# Power.net
KiCad netlist of a schematic drawn in Altium Designer
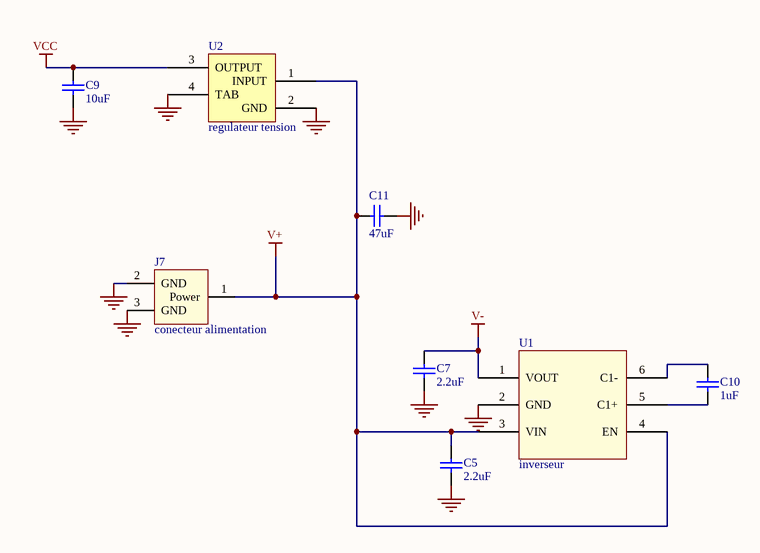
[diagram p0: Power.SchDoc]

(export (version "E")
  (design (tool "Eeschema 10.0.6"))
  (components
    (comp (ref "C5")
      (value "2.2uF")
      (footprint "CAPC1608X09N")
      (description "Capacitor")
      (fields (field (name "PUBLISHER") "Altium Limited"))
      (libsource (lib "Miscellaneous Devices") (part "Cap"))
    )
    (comp (ref "C7")
      (value "2.2uF")
      (footprint "CAPC1608X09N")
      (description "Capacitor")
      (fields (field (name "PUBLISHER") "Altium Limited"))
      (libsource (lib "Miscellaneous Devices") (part "Cap"))
    )
    (comp (ref "C9")
      (value "10uF")
      (footprint "CAPC1608X09N")
      (description "Capacitor")
      (fields (field (name "PUBLISHER") "Altium Limited"))
      (libsource (lib "Miscellaneous Devices") (part "Cap"))
    )
    (comp (ref "C10")
      (value "1uF")
      (footprint "CAPC1608X09N")
      (description "Capacitor")
      (fields (field (name "PUBLISHER") "Altium Limited"))
      (libsource (lib "Miscellaneous Devices") (part "Cap"))
    )
    (comp (ref "C11")
      (value "47uF")
      (footprint "CAPC1608X09N")
      (description "Capacitor")
      (fields (field (name "PUBLISHER") "Altium Limited"))
      (libsource (lib "Miscellaneous Devices") (part "Cap"))
    )
    (comp (ref "J7")
      (value "conecteur alimentation")
      (libsource (lib "lib_protoboard") (part "conecteur alimentation"))
    )
    (comp (ref "U1") (value "inverseur") (libsource (lib "lib_protoboard") (part "inverseur")))
    (comp (ref "U2")
      (value "regulateur tension")
      (footprint "SOT230P710X180-4N")
      (libsource (lib "lib_protoboard") (part "regulateur tension"))
    )
  )
  (nets
    (net (code "1") (name "GND") (class "Default")
      (node (ref "C11") (pin "1") (pinfunction "1_1") (pintype "passive"))
      (node (ref "C5") (pin "1") (pinfunction "1_1") (pintype "passive"))
      (node (ref "C7") (pin "1") (pinfunction "1_1") (pintype "passive"))
      (node (ref "C9") (pin "1") (pinfunction "1_1") (pintype "passive"))
      (node (ref "J7") (pin "2") (pinfunction "GND_2") (pintype "passive"))
      (node (ref "J7") (pin "3") (pinfunction "GND_3") (pintype "passive"))
      (node (ref "U1") (pin "2") (pinfunction "GND_2") (pintype "passive"))
      (node (ref "U2") (pin "2") (pinfunction "GND_2") (pintype "passive"))
      (node (ref "U2") (pin "4") (pinfunction "TAB_4") (pintype "passive"))
    )
    (net (code "2") (name "Net-(U1-C1+)") (class "Default")
      (node (ref "C10") (pin "2") (pinfunction "2_2") (pintype "passive"))
      (node (ref "U1") (pin "5") (pinfunction "C1+_5") (pintype "passive"))
    )
    (net (code "3") (name "Net-(U1-C1-)") (class "Default")
      (node (ref "C10") (pin "1") (pinfunction "1_1") (pintype "passive"))
      (node (ref "U1") (pin "6") (pinfunction "C1-_6") (pintype "passive"))
    )
    (net (code "4") (name "V+") (class "Default")
      (node (ref "C11") (pin "2") (pinfunction "2_2") (pintype "passive"))
      (node (ref "C5") (pin "2") (pinfunction "2_2") (pintype "passive"))
      (node (ref "J7") (pin "1") (pinfunction "Power_1") (pintype "power_in"))
      (node (ref "U1") (pin "3") (pinfunction "VIN_3") (pintype "passive"))
      (node (ref "U1") (pin "4") (pinfunction "EN_4") (pintype "passive"))
      (node (ref "U2") (pin "1") (pinfunction "INPUT_1") (pintype "passive"))
    )
    (net (code "5") (name "V-") (class "Default")
      (node (ref "C7") (pin "2") (pinfunction "2_2") (pintype "passive"))
      (node (ref "U1") (pin "1") (pinfunction "VOUT_1") (pintype "passive"))
    )
    (net (code "6") (name "VCC") (class "Default")
      (node (ref "C9") (pin "2") (pinfunction "2_2") (pintype "passive"))
      (node (ref "U2") (pin "3") (pinfunction "OUTPUT_3") (pintype "passive"))
    )
  )
)
